# testSchematic.net
KiCad netlist of a schematic drawn in EAGLE
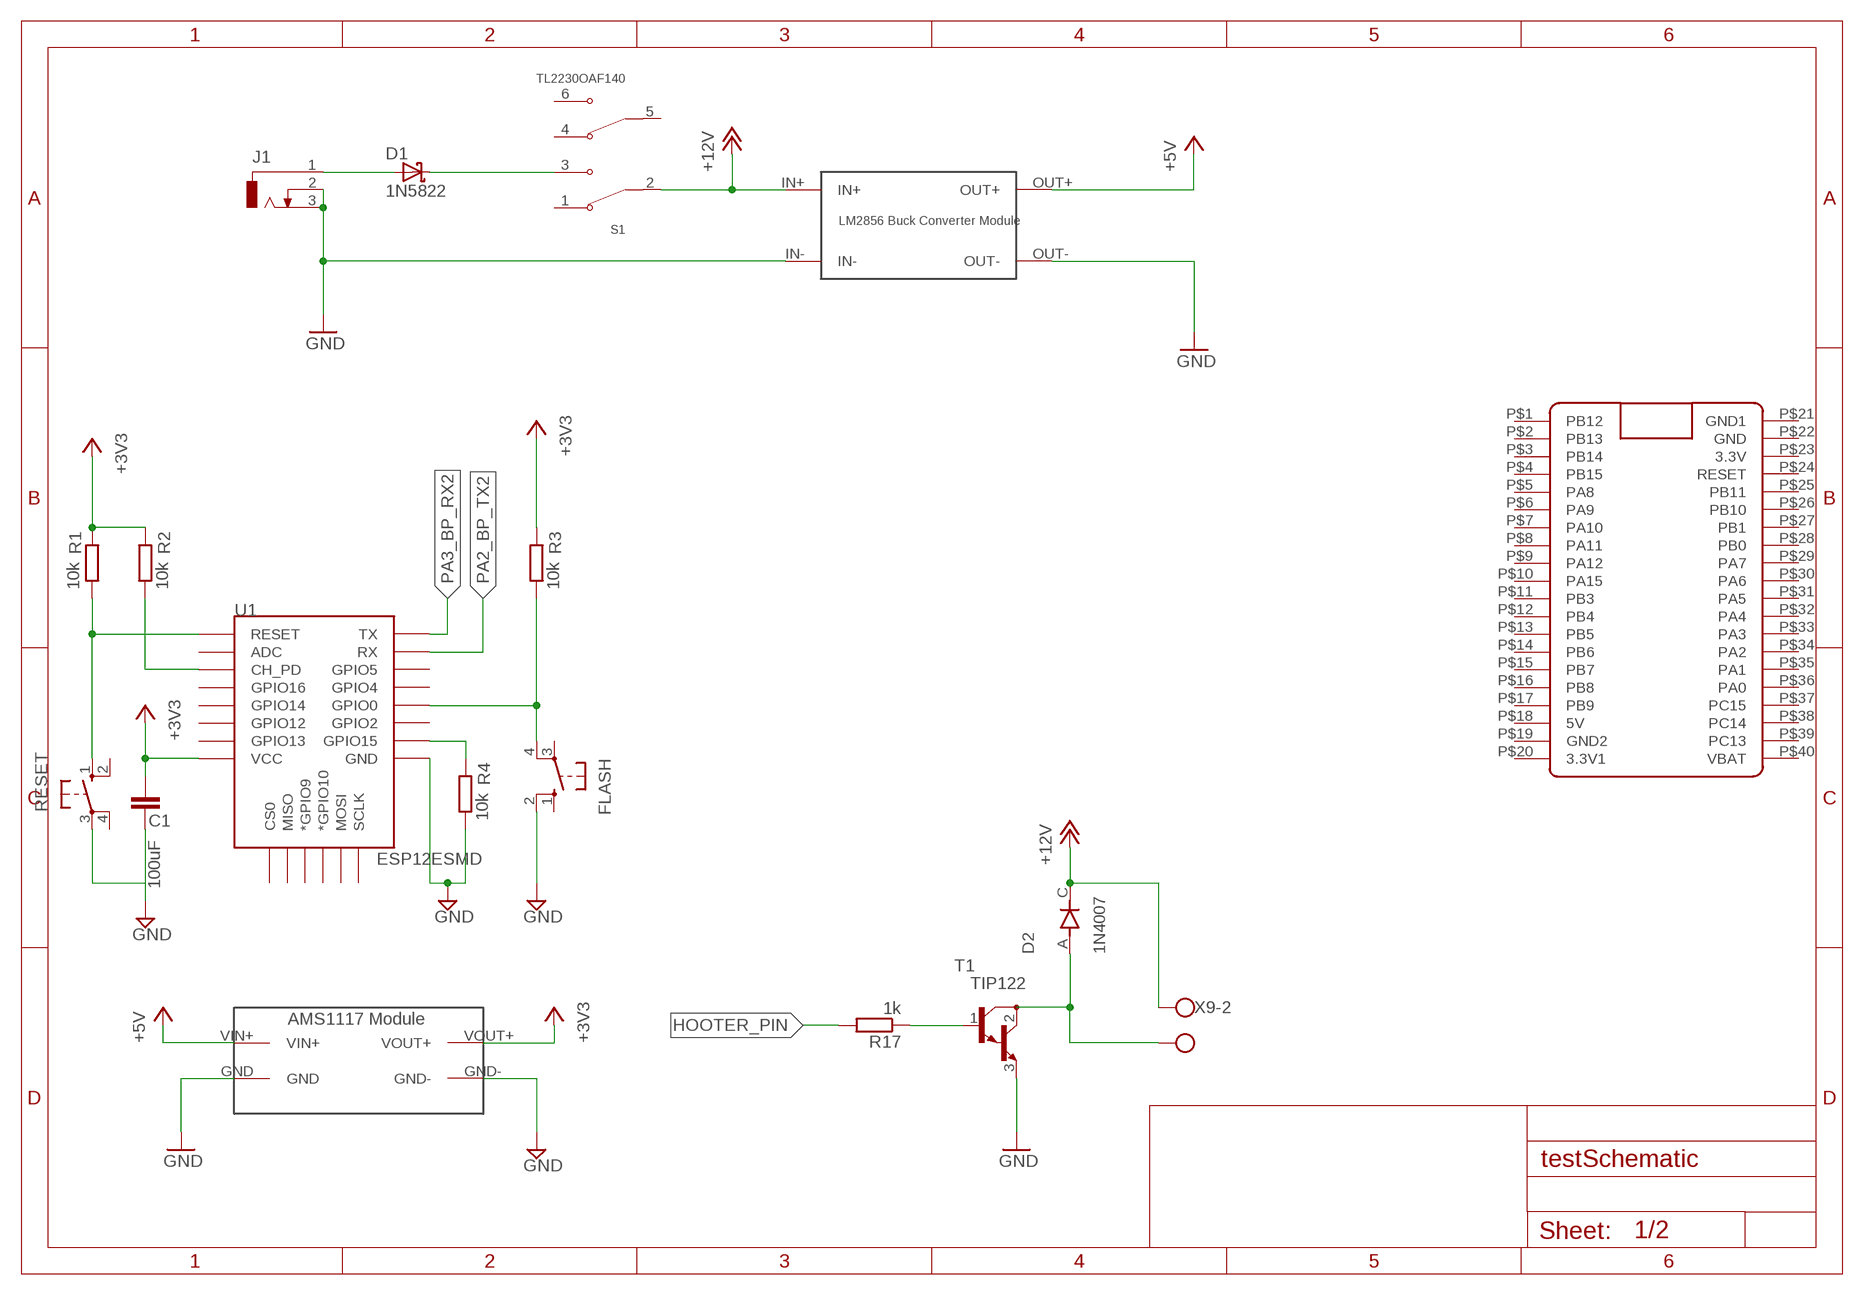
[diagram p0: schematic, sheet 1]
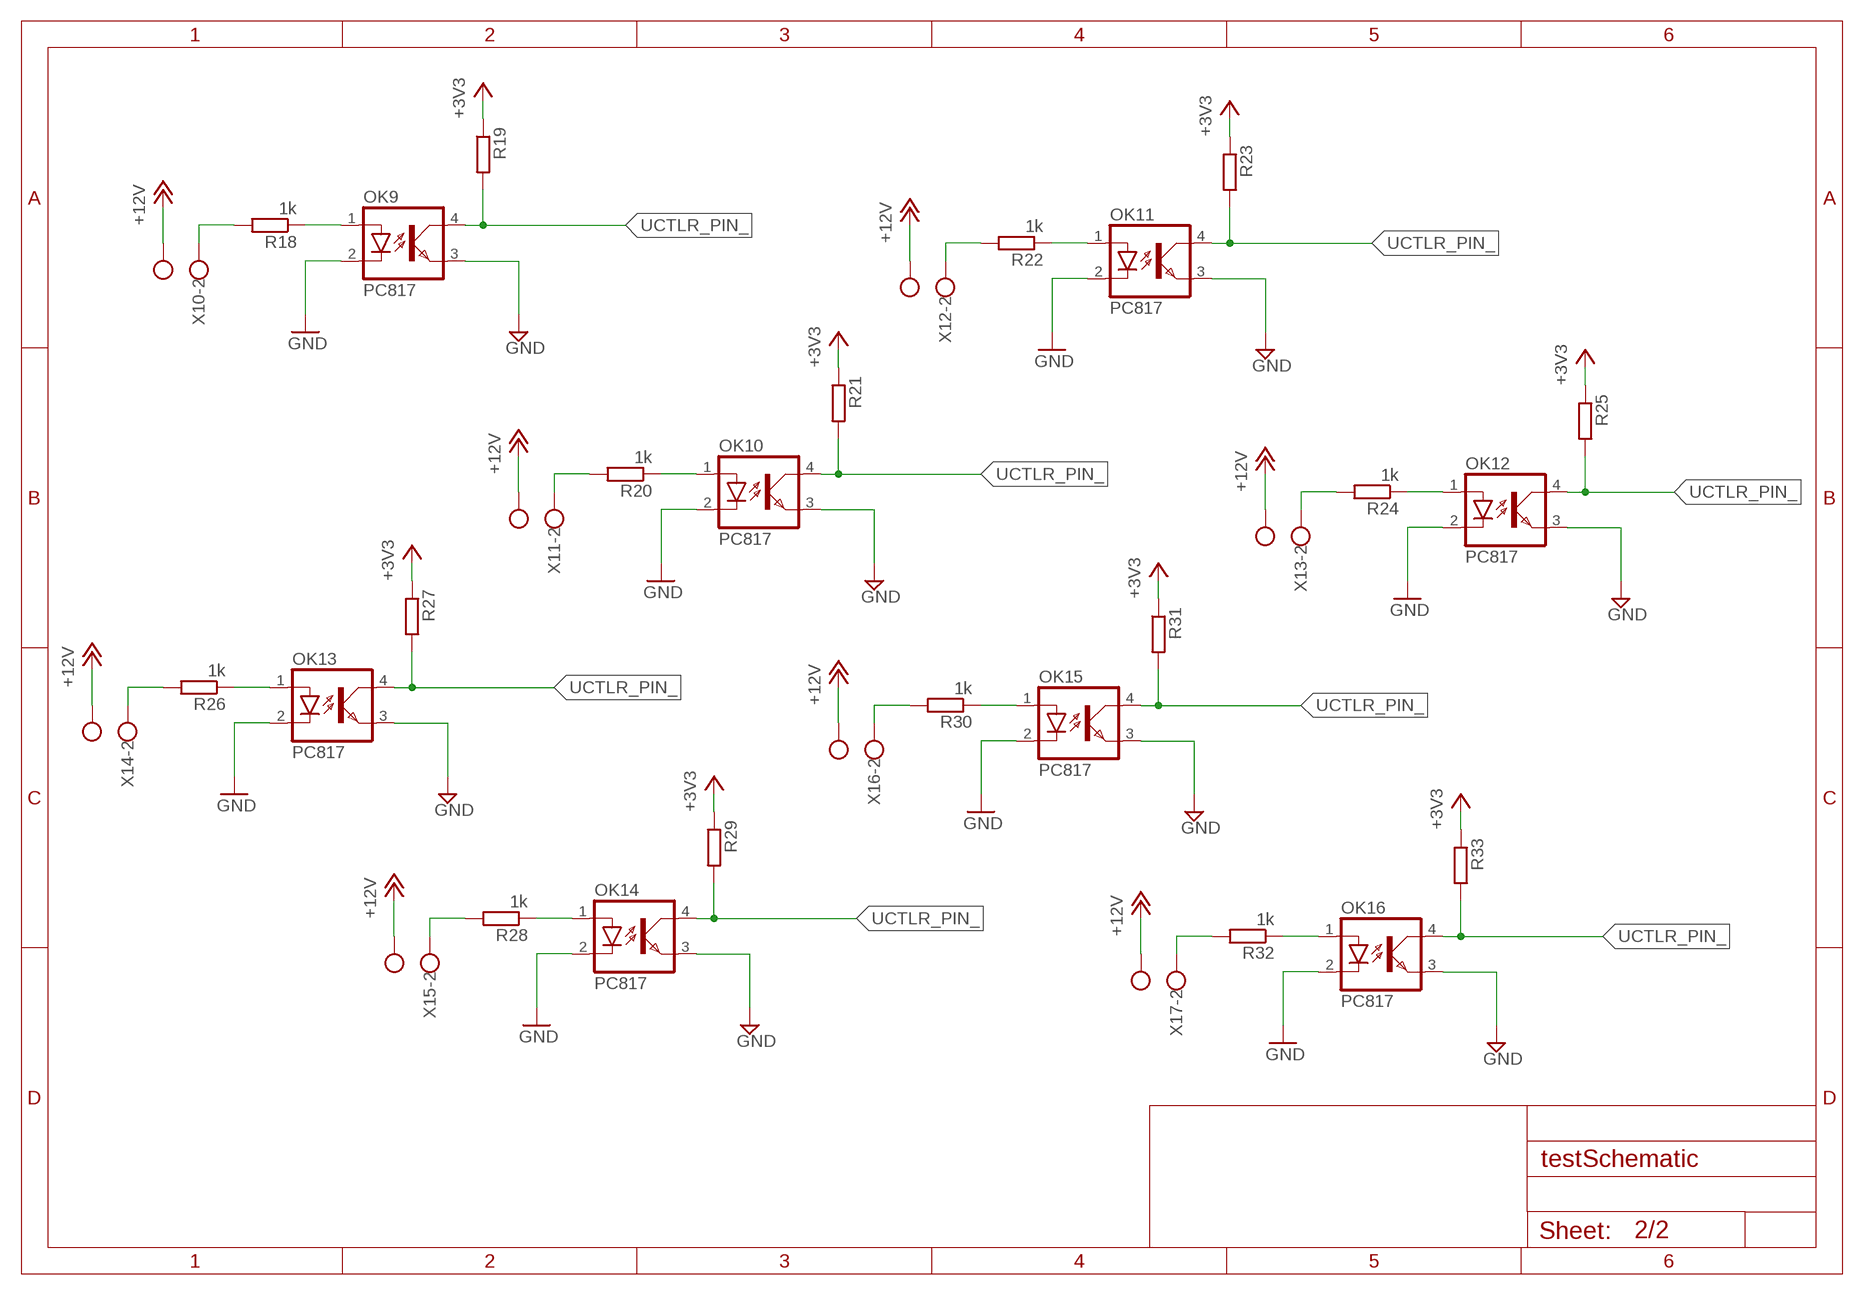
[diagram p1: schematic, sheet 2]

(export (version "E")
  (design (tool "Eeschema 10.0.6"))
  (components
    (comp (ref "C1")
      (value "100uF")
      (footprint "eagle-import:C2.5-3")
      (libsource (lib "eagle-import") (part "C2,5-3"))
    )
    (comp (ref "D1")
      (value "1N5822")
      (footprint "eagle-import:DIOAD2120W130L950D530P")
      (fields (field (name "MF") "ON Semiconductor"))
      (libsource (lib "eagle-import") (part "1N5822"))
    )
    (comp (ref "D2")
      (value "1N4007")
      (footprint "eagle-import:DIOAD1060W80L520D270")
      (fields (field (name "MF") "ON Semiconductor"))
      (libsource (lib "eagle-import") (part "1N4007"))
    )
    (comp (ref "FLASH")
      (value "10-XX")
      (footprint "eagle-import:B3F-10XX")
      (fields (field (name "MPN") "B3F-1000"))
      (libsource (lib "eagle-import") (part "10-XX"))
    )
    (comp (ref "J1")
      (value "DCJ0303")
      (footprint "eagle-import:DCJ0303")
      (libsource (lib "eagle-import") (part "DCJ0303"))
    )
    (comp (ref "R1")
      (value "10k")
      (footprint "eagle-import:0207_10")
      (libsource (lib "eagle-import") (part "R-EU_0207/10"))
    )
    (comp (ref "R2")
      (value "10k")
      (footprint "eagle-import:0207_10")
      (libsource (lib "eagle-import") (part "R-EU_0207/10"))
    )
    (comp (ref "R3")
      (value "10k")
      (footprint "eagle-import:0207_10")
      (libsource (lib "eagle-import") (part "R-EU_0207/10"))
    )
    (comp (ref "R4")
      (value "10k")
      (footprint "eagle-import:0207_10")
      (libsource (lib "eagle-import") (part "R-EU_0207/10"))
    )
    (comp (ref "R17")
      (value "1k")
      (footprint "eagle-import:0204_7")
      (libsource (lib "eagle-import") (part "R-EU_0204/7"))
    )
    (comp (ref "RESET")
      (value "10-XX")
      (footprint "eagle-import:B3F-10XX")
      (fields (field (name "MPN") "B3F-1000"))
      (libsource (lib "eagle-import") (part "10-XX"))
    )
    (comp (ref "S1")
      (value "TL2230OAF140")
      (footprint "eagle-import:SW_TL2230OAF140")
      (fields (field (name "MF") "E-Switch"))
      (libsource (lib "eagle-import") (part "TL2230OAF140"))
    )
    (comp (ref "T1")
      (value "TIP122")
      (footprint "eagle-import:TO220")
      (fields (field (name "MF") "onsemi"))
      (libsource (lib "eagle-import") (part "TIP122"))
    )
    (comp (ref "U$1")
      (value "BLUE_PILL")
      (footprint "eagle-import:BLUE_PILL")
      (libsource (lib "eagle-import") (part "BLUE_PILL"))
    )
    (comp (ref "U$2")
      (value "LM2596_MODULELM2569_MODULE")
      (footprint "eagle-import:LM2596_MODULE")
      (libsource (lib "eagle-import") (part "LM2596_MODULELM2569_MODULE"))
    )
    (comp (ref "U$3")
      (value "AMS1117_MODULE")
      (footprint "eagle-import:AMS1117_MODULE")
      (libsource (lib "eagle-import") (part "AMS1117_MODULE"))
    )
    (comp (ref "U1")
      (value "ESP12ESMD")
      (footprint "eagle-import:ESP12E-SMD")
      (fields (field (name "MF") "AI-Thinker") (field (name "MP") "ESP-12E"))
      (libsource (lib "eagle-import") (part "ESP12ESMD"))
    )
    (comp (ref "X9")
      (value "W237-102")
      (footprint "eagle-import:W237-102")
      (fields (field (name "MPN") "237-102"))
      (libsource (lib "eagle-import") (part "W237-102"))
    )
    (comp (ref "OK9")
      (value "PC817")
      (footprint "eagle-import:DIL04")
      (fields (field (name "MPN") "PC817X4J000F"))
      (libsource (lib "eagle-import") (part "PC817"))
    )
    (comp (ref "OK10")
      (value "PC817")
      (footprint "eagle-import:DIL04")
      (fields (field (name "MPN") "PC817X4J000F"))
      (libsource (lib "eagle-import") (part "PC817"))
    )
    (comp (ref "OK11")
      (value "PC817")
      (footprint "eagle-import:DIL04")
      (fields (field (name "MPN") "PC817X4J000F"))
      (libsource (lib "eagle-import") (part "PC817"))
    )
    (comp (ref "OK12")
      (value "PC817")
      (footprint "eagle-import:DIL04")
      (fields (field (name "MPN") "PC817X4J000F"))
      (libsource (lib "eagle-import") (part "PC817"))
    )
    (comp (ref "OK13")
      (value "PC817")
      (footprint "eagle-import:DIL04")
      (fields (field (name "MPN") "PC817X4J000F"))
      (libsource (lib "eagle-import") (part "PC817"))
    )
    (comp (ref "OK14")
      (value "PC817")
      (footprint "eagle-import:DIL04")
      (fields (field (name "MPN") "PC817X4J000F"))
      (libsource (lib "eagle-import") (part "PC817"))
    )
    (comp (ref "OK15")
      (value "PC817")
      (footprint "eagle-import:DIL04")
      (fields (field (name "MPN") "PC817X4J000F"))
      (libsource (lib "eagle-import") (part "PC817"))
    )
    (comp (ref "OK16")
      (value "PC817")
      (footprint "eagle-import:DIL04")
      (fields (field (name "MPN") "PC817X4J000F"))
      (libsource (lib "eagle-import") (part "PC817"))
    )
    (comp (ref "R18")
      (value "1k")
      (footprint "eagle-import:0204_7")
      (libsource (lib "eagle-import") (part "R-EU_0204/7"))
    )
    (comp (ref "R19")
      (value "R-EU_0204/7")
      (footprint "eagle-import:0204_7")
      (libsource (lib "eagle-import") (part "R-EU_0204/7"))
    )
    (comp (ref "R20")
      (value "1k")
      (footprint "eagle-import:0204_7")
      (libsource (lib "eagle-import") (part "R-EU_0204/7"))
    )
    (comp (ref "R21")
      (value "R-EU_0204/7")
      (footprint "eagle-import:0204_7")
      (libsource (lib "eagle-import") (part "R-EU_0204/7"))
    )
    (comp (ref "R22")
      (value "1k")
      (footprint "eagle-import:0204_7")
      (libsource (lib "eagle-import") (part "R-EU_0204/7"))
    )
    (comp (ref "R23")
      (value "R-EU_0204/7")
      (footprint "eagle-import:0204_7")
      (libsource (lib "eagle-import") (part "R-EU_0204/7"))
    )
    (comp (ref "R24")
      (value "1k")
      (footprint "eagle-import:0204_7")
      (libsource (lib "eagle-import") (part "R-EU_0204/7"))
    )
    (comp (ref "R25")
      (value "R-EU_0204/7")
      (footprint "eagle-import:0204_7")
      (libsource (lib "eagle-import") (part "R-EU_0204/7"))
    )
    (comp (ref "R26")
      (value "1k")
      (footprint "eagle-import:0204_7")
      (libsource (lib "eagle-import") (part "R-EU_0204/7"))
    )
    (comp (ref "R27")
      (value "R-EU_0204/7")
      (footprint "eagle-import:0204_7")
      (libsource (lib "eagle-import") (part "R-EU_0204/7"))
    )
    (comp (ref "R28")
      (value "1k")
      (footprint "eagle-import:0204_7")
      (libsource (lib "eagle-import") (part "R-EU_0204/7"))
    )
    (comp (ref "R29")
      (value "R-EU_0204/7")
      (footprint "eagle-import:0204_7")
      (libsource (lib "eagle-import") (part "R-EU_0204/7"))
    )
    (comp (ref "R30")
      (value "1k")
      (footprint "eagle-import:0204_7")
      (libsource (lib "eagle-import") (part "R-EU_0204/7"))
    )
    (comp (ref "R31")
      (value "R-EU_0204/7")
      (footprint "eagle-import:0204_7")
      (libsource (lib "eagle-import") (part "R-EU_0204/7"))
    )
    (comp (ref "R32")
      (value "1k")
      (footprint "eagle-import:0204_7")
      (libsource (lib "eagle-import") (part "R-EU_0204/7"))
    )
    (comp (ref "R33")
      (value "R-EU_0204/7")
      (footprint "eagle-import:0204_7")
      (libsource (lib "eagle-import") (part "R-EU_0204/7"))
    )
    (comp (ref "X10")
      (value "W237-102")
      (footprint "eagle-import:W237-102")
      (fields (field (name "MPN") "237-102"))
      (libsource (lib "eagle-import") (part "W237-102"))
    )
    (comp (ref "X11")
      (value "W237-102")
      (footprint "eagle-import:W237-102")
      (fields (field (name "MPN") "237-102"))
      (libsource (lib "eagle-import") (part "W237-102"))
    )
    (comp (ref "X12")
      (value "W237-102")
      (footprint "eagle-import:W237-102")
      (fields (field (name "MPN") "237-102"))
      (libsource (lib "eagle-import") (part "W237-102"))
    )
    (comp (ref "X13")
      (value "W237-102")
      (footprint "eagle-import:W237-102")
      (fields (field (name "MPN") "237-102"))
      (libsource (lib "eagle-import") (part "W237-102"))
    )
    (comp (ref "X14")
      (value "W237-102")
      (footprint "eagle-import:W237-102")
      (fields (field (name "MPN") "237-102"))
      (libsource (lib "eagle-import") (part "W237-102"))
    )
    (comp (ref "X15")
      (value "W237-102")
      (footprint "eagle-import:W237-102")
      (fields (field (name "MPN") "237-102"))
      (libsource (lib "eagle-import") (part "W237-102"))
    )
    (comp (ref "X16")
      (value "W237-102")
      (footprint "eagle-import:W237-102")
      (fields (field (name "MPN") "237-102"))
      (libsource (lib "eagle-import") (part "W237-102"))
    )
    (comp (ref "X17")
      (value "W237-102")
      (footprint "eagle-import:W237-102")
      (fields (field (name "MPN") "237-102"))
      (libsource (lib "eagle-import") (part "W237-102"))
    )
  )
  (nets
    (net (code "1") (name "+3V3") (class "Default")
      (node (ref "C1") (pin "2") (pinfunction "2_2") (pintype "passive"))
      (node (ref "R1") (pin "2") (pinfunction "2_2") (pintype "passive"))
      (node (ref "R19") (pin "1") (pinfunction "1_1") (pintype "passive"))
      (node (ref "R2") (pin "2") (pinfunction "2_2") (pintype "passive"))
      (node (ref "R21") (pin "1") (pinfunction "1_1") (pintype "passive"))
      (node (ref "R23") (pin "1") (pinfunction "1_1") (pintype "passive"))
      (node (ref "R25") (pin "1") (pinfunction "1_1") (pintype "passive"))
      (node (ref "R27") (pin "1") (pinfunction "1_1") (pintype "passive"))
      (node (ref "R29") (pin "1") (pinfunction "1_1") (pintype "passive"))
      (node (ref "R3") (pin "2") (pinfunction "2_2") (pintype "passive"))
      (node (ref "R31") (pin "1") (pinfunction "1_1") (pintype "passive"))
      (node (ref "R33") (pin "1") (pinfunction "1_1") (pintype "passive"))
      (node (ref "U$3") (pin "VOUT+") (pinfunction "VOUT+_VOUT+") (pintype "bidirectional"))
      (node (ref "U1") (pin "VCC") (pinfunction "VCC_VCC") (pintype "bidirectional"))
    )
    (net (code "2") (name "+5V") (class "Default")
      (node (ref "U$2") (pin "OUT+") (pinfunction "OUT+_OUT+") (pintype "bidirectional"))
      (node (ref "U$3") (pin "VIN+") (pinfunction "VIN+_VIN+") (pintype "bidirectional"))
    )
    (net (code "3") (name "+12V") (class "Default")
      (node (ref "D2") (pin "C") (pinfunction "C_C") (pintype "passive"))
      (node (ref "S1") (pin "2") (pinfunction "COM1_2") (pintype "passive"))
      (node (ref "U$2") (pin "IN+") (pinfunction "IN+_IN+") (pintype "bidirectional"))
      (node (ref "X10") (pin "1") (pinfunction "KL_1") (pintype "passive"))
      (node (ref "X11") (pin "1") (pinfunction "KL_1") (pintype "passive"))
      (node (ref "X12") (pin "1") (pinfunction "KL_1") (pintype "passive"))
      (node (ref "X13") (pin "1") (pinfunction "KL_1") (pintype "passive"))
      (node (ref "X14") (pin "1") (pinfunction "KL_1") (pintype "passive"))
      (node (ref "X15") (pin "1") (pinfunction "KL_1") (pintype "passive"))
      (node (ref "X16") (pin "1") (pinfunction "KL_1") (pintype "passive"))
      (node (ref "X17") (pin "1") (pinfunction "KL_1") (pintype "passive"))
      (node (ref "X9") (pin "2") (pinfunction "KL_2") (pintype "passive"))
    )
    (net (code "4") (name "GND") (class "Default")
      (node (ref "C1") (pin "1") (pinfunction "1_1") (pintype "passive"))
      (node (ref "FLASH") (pin "2") (pinfunction "S1_2") (pintype "passive"))
      (node (ref "J1") (pin "2") (pinfunction "2_2") (pintype "passive"))
      (node (ref "J1") (pin "3") (pinfunction "3_3") (pintype "passive"))
      (node (ref "OK10") (pin "2") (pinfunction "C_2") (pintype "passive"))
      (node (ref "OK10") (pin "3") (pinfunction "EMIT_3") (pintype "passive"))
      (node (ref "OK11") (pin "2") (pinfunction "C_2") (pintype "passive"))
      (node (ref "OK11") (pin "3") (pinfunction "EMIT_3") (pintype "passive"))
      (node (ref "OK12") (pin "2") (pinfunction "C_2") (pintype "passive"))
      (node (ref "OK12") (pin "3") (pinfunction "EMIT_3") (pintype "passive"))
      (node (ref "OK13") (pin "2") (pinfunction "C_2") (pintype "passive"))
      (node (ref "OK13") (pin "3") (pinfunction "EMIT_3") (pintype "passive"))
      (node (ref "OK14") (pin "2") (pinfunction "C_2") (pintype "passive"))
      (node (ref "OK14") (pin "3") (pinfunction "EMIT_3") (pintype "passive"))
      (node (ref "OK15") (pin "2") (pinfunction "C_2") (pintype "passive"))
      (node (ref "OK15") (pin "3") (pinfunction "EMIT_3") (pintype "passive"))
      (node (ref "OK16") (pin "2") (pinfunction "C_2") (pintype "passive"))
      (node (ref "OK16") (pin "3") (pinfunction "EMIT_3") (pintype "passive"))
      (node (ref "OK9") (pin "2") (pinfunction "C_2") (pintype "passive"))
      (node (ref "OK9") (pin "3") (pinfunction "EMIT_3") (pintype "passive"))
      (node (ref "R4") (pin "1") (pinfunction "1_1") (pintype "passive"))
      (node (ref "RESET") (pin "3") (pinfunction "P_3") (pintype "passive"))
      (node (ref "T1") (pin "3") (pinfunction "E_3") (pintype "passive"))
      (node (ref "U$2") (pin "IN-") (pinfunction "IN-_IN-") (pintype "bidirectional"))
      (node (ref "U$2") (pin "OUT-") (pinfunction "OUT-_OUT-") (pintype "bidirectional"))
      (node (ref "U$3") (pin "GND") (pinfunction "GND_GND") (pintype "bidirectional"))
      (node (ref "U$3") (pin "GND-") (pinfunction "GND-_GND-") (pintype "bidirectional"))
      (node (ref "U1") (pin "GND") (pinfunction "GND_GND") (pintype "bidirectional"))
    )
    (net (code "5") (name "GND1") (class "Default")
      (node (ref "U$1") (pin "P$21") (pinfunction "GND1_P$21") (pintype "power_in"))
    )
    (net (code "6") (name "HOOTER_PIN") (class "Default")
      (node (ref "R17") (pin "2") (pinfunction "2_2") (pintype "passive"))
    )
    (net (code "7") (name "Net-(D1-PadA)") (class "Default")
      (node (ref "D1") (pin "A") (pinfunction "A_A") (pintype "passive"))
      (node (ref "J1") (pin "1") (pinfunction "1_1") (pintype "passive"))
    )
    (net (code "8") (name "Net-(FLASH-P1)") (class "Default")
      (node (ref "FLASH") (pin "4") (pinfunction "P1_4") (pintype "passive"))
      (node (ref "R3") (pin "1") (pinfunction "1_1") (pintype "passive"))
      (node (ref "U1") (pin "GPIO0") (pinfunction "GPIO0_GPIO0") (pintype "bidirectional"))
    )
    (net (code "9") (name "Net-(OK9-A)") (class "Default")
      (node (ref "OK9") (pin "1") (pinfunction "A_1") (pintype "passive"))
      (node (ref "R18") (pin "1") (pinfunction "1_1") (pintype "passive"))
    )
    (net (code "10") (name "Net-(OK10-A)") (class "Default")
      (node (ref "OK10") (pin "1") (pinfunction "A_1") (pintype "passive"))
      (node (ref "R20") (pin "1") (pinfunction "1_1") (pintype "passive"))
    )
    (net (code "11") (name "Net-(OK11-A)") (class "Default")
      (node (ref "OK11") (pin "1") (pinfunction "A_1") (pintype "passive"))
      (node (ref "R22") (pin "1") (pinfunction "1_1") (pintype "passive"))
    )
    (net (code "12") (name "Net-(OK12-A)") (class "Default")
      (node (ref "OK12") (pin "1") (pinfunction "A_1") (pintype "passive"))
      (node (ref "R24") (pin "1") (pinfunction "1_1") (pintype "passive"))
    )
    (net (code "13") (name "Net-(OK13-A)") (class "Default")
      (node (ref "OK13") (pin "1") (pinfunction "A_1") (pintype "passive"))
      (node (ref "R26") (pin "1") (pinfunction "1_1") (pintype "passive"))
    )
    (net (code "14") (name "Net-(OK14-A)") (class "Default")
      (node (ref "OK14") (pin "1") (pinfunction "A_1") (pintype "passive"))
      (node (ref "R28") (pin "1") (pinfunction "1_1") (pintype "passive"))
    )
    (net (code "15") (name "Net-(OK15-A)") (class "Default")
      (node (ref "OK15") (pin "1") (pinfunction "A_1") (pintype "passive"))
      (node (ref "R30") (pin "1") (pinfunction "1_1") (pintype "passive"))
    )
    (net (code "16") (name "Net-(OK16-A)") (class "Default")
      (node (ref "OK16") (pin "1") (pinfunction "A_1") (pintype "passive"))
      (node (ref "R32") (pin "1") (pinfunction "1_1") (pintype "passive"))
    )
    (net (code "17") (name "Net-(R2-Pad1)") (class "Default")
      (node (ref "R2") (pin "1") (pinfunction "1_1") (pintype "passive"))
      (node (ref "U1") (pin "CH_PD") (pinfunction "CH_PD_CH_PD") (pintype "bidirectional"))
    )
    (net (code "18") (name "Net-(R4-Pad2)") (class "Default")
      (node (ref "R4") (pin "2") (pinfunction "2_2") (pintype "passive"))
      (node (ref "U1") (pin "GPIO15") (pinfunction "GPIO15_GPIO15") (pintype "bidirectional"))
    )
    (net (code "19") (name "Net-(RESET-S)") (class "Default")
      (node (ref "R1") (pin "1") (pinfunction "1_1") (pintype "passive"))
      (node (ref "RESET") (pin "1") (pinfunction "S_1") (pintype "passive"))
      (node (ref "U1") (pin "RESET") (pinfunction "RESET_RESET") (pintype "bidirectional"))
    )
    (net (code "20") (name "Net-(S1-NO1)") (class "Default")
      (node (ref "D1") (pin "C") (pinfunction "C_C") (pintype "passive"))
      (node (ref "S1") (pin "3") (pinfunction "NO1_3") (pintype "passive"))
    )
    (net (code "21") (name "Net-(T1-B)") (class "Default")
      (node (ref "R17") (pin "1") (pinfunction "1_1") (pintype "passive"))
      (node (ref "T1") (pin "1") (pinfunction "B_1") (pintype "passive"))
    )
    (net (code "22") (name "Net-(T1-C)") (class "Default")
      (node (ref "D2") (pin "A") (pinfunction "A_A") (pintype "passive"))
      (node (ref "T1") (pin "2") (pinfunction "C_2") (pintype "passive"))
      (node (ref "X9") (pin "1") (pinfunction "KL_1") (pintype "passive"))
    )
    (net (code "23") (name "Net-(X10B-KL)") (class "Default")
      (node (ref "R18") (pin "2") (pinfunction "2_2") (pintype "passive"))
      (node (ref "X10") (pin "2") (pinfunction "KL_2") (pintype "passive"))
    )
    (net (code "24") (name "Net-(X11B-KL)") (class "Default")
      (node (ref "R20") (pin "2") (pinfunction "2_2") (pintype "passive"))
      (node (ref "X11") (pin "2") (pinfunction "KL_2") (pintype "passive"))
    )
    (net (code "25") (name "Net-(X12B-KL)") (class "Default")
      (node (ref "R22") (pin "2") (pinfunction "2_2") (pintype "passive"))
      (node (ref "X12") (pin "2") (pinfunction "KL_2") (pintype "passive"))
    )
    (net (code "26") (name "Net-(X13B-KL)") (class "Default")
      (node (ref "R24") (pin "2") (pinfunction "2_2") (pintype "passive"))
      (node (ref "X13") (pin "2") (pinfunction "KL_2") (pintype "passive"))
    )
    (net (code "27") (name "Net-(X14B-KL)") (class "Default")
      (node (ref "R26") (pin "2") (pinfunction "2_2") (pintype "passive"))
      (node (ref "X14") (pin "2") (pinfunction "KL_2") (pintype "passive"))
    )
    (net (code "28") (name "Net-(X15B-KL)") (class "Default")
      (node (ref "R28") (pin "2") (pinfunction "2_2") (pintype "passive"))
      (node (ref "X15") (pin "2") (pinfunction "KL_2") (pintype "passive"))
    )
    (net (code "29") (name "Net-(X16B-KL)") (class "Default")
      (node (ref "R30") (pin "2") (pinfunction "2_2") (pintype "passive"))
      (node (ref "X16") (pin "2") (pinfunction "KL_2") (pintype "passive"))
    )
    (net (code "30") (name "Net-(X17B-KL)") (class "Default")
      (node (ref "R32") (pin "2") (pinfunction "2_2") (pintype "passive"))
      (node (ref "X17") (pin "2") (pinfunction "KL_2") (pintype "passive"))
    )
    (net (code "31") (name "PA2_BP_TX2") (class "Default")
      (node (ref "U1") (pin "RXD0") (pinfunction "RX_RXD0") (pintype "bidirectional"))
    )
    (net (code "32") (name "PA3_BP_RX2") (class "Default")
      (node (ref "U1") (pin "TXD0") (pinfunction "TX_TXD0") (pintype "bidirectional"))
    )
    (net (code "33") (name "UCTLR_PIN_") (class "Default")
      (node (ref "OK10") (pin "4") (pinfunction "COL_4") (pintype "passive"))
      (node (ref "OK11") (pin "4") (pinfunction "COL_4") (pintype "passive"))
      (node (ref "OK12") (pin "4") (pinfunction "COL_4") (pintype "passive"))
      (node (ref "OK13") (pin "4") (pinfunction "COL_4") (pintype "passive"))
      (node (ref "OK14") (pin "4") (pinfunction "COL_4") (pintype "passive"))
      (node (ref "OK15") (pin "4") (pinfunction "COL_4") (pintype "passive"))
      (node (ref "OK16") (pin "4") (pinfunction "COL_4") (pintype "passive"))
      (node (ref "OK9") (pin "4") (pinfunction "COL_4") (pintype "passive"))
      (node (ref "R19") (pin "2") (pinfunction "2_2") (pintype "passive"))
      (node (ref "R21") (pin "2") (pinfunction "2_2") (pintype "passive"))
      (node (ref "R23") (pin "2") (pinfunction "2_2") (pintype "passive"))
      (node (ref "R25") (pin "2") (pinfunction "2_2") (pintype "passive"))
      (node (ref "R27") (pin "2") (pinfunction "2_2") (pintype "passive"))
      (node (ref "R29") (pin "2") (pinfunction "2_2") (pintype "passive"))
      (node (ref "R31") (pin "2") (pinfunction "2_2") (pintype "passive"))
      (node (ref "R33") (pin "2") (pinfunction "2_2") (pintype "passive"))
    )
    (net (code "34") (name "unconnected-(FLASH-P-Pad3)") (class "Default")
      (node (ref "FLASH") (pin "3") (pinfunction "P_3") (pintype "passive"))
    )
    (net (code "35") (name "unconnected-(FLASH-S-Pad1)") (class "Default")
      (node (ref "FLASH") (pin "1") (pinfunction "S_1") (pintype "passive"))
    )
    (net (code "36") (name "unconnected-(RESET-P1-Pad4)") (class "Default")
      (node (ref "RESET") (pin "4") (pinfunction "P1_4") (pintype "passive"))
    )
    (net (code "37") (name "unconnected-(RESET-S1-Pad2)") (class "Default")
      (node (ref "RESET") (pin "2") (pinfunction "S1_2") (pintype "passive"))
    )
    (net (code "38") (name "unconnected-(S1-COM2-Pad5)") (class "Default")
      (node (ref "S1") (pin "5") (pinfunction "COM2_5") (pintype "passive"))
    )
    (net (code "39") (name "unconnected-(S1-NC1-Pad1)") (class "Default")
      (node (ref "S1") (pin "1") (pinfunction "NC1_1") (pintype "passive"))
    )
    (net (code "40") (name "unconnected-(S1-NC2-Pad4)") (class "Default")
      (node (ref "S1") (pin "4") (pinfunction "NC2_4") (pintype "passive"))
    )
    (net (code "41") (name "unconnected-(S1-NO2-Pad6)") (class "Default")
      (node (ref "S1") (pin "6") (pinfunction "NO2_6") (pintype "passive"))
    )
    (net (code "42") (name "unconnected-(U$1-3.3V-PadP$23)") (class "Default")
      (node (ref "U$1") (pin "P$23") (pinfunction "3.3V_P$23") (pintype "bidirectional"))
    )
    (net (code "43") (name "unconnected-(U$1-3.3V1-PadP$20)") (class "Default")
      (node (ref "U$1") (pin "P$20") (pinfunction "3.3V1_P$20") (pintype "bidirectional"))
    )
    (net (code "44") (name "unconnected-(U$1-5V-PadP$18)") (class "Default")
      (node (ref "U$1") (pin "P$18") (pinfunction "5V_P$18") (pintype "bidirectional"))
    )
    (net (code "45") (name "unconnected-(U$1-GND-PadP$22)") (class "Default")
      (node (ref "U$1") (pin "P$22") (pinfunction "GND_P$22") (pintype "bidirectional"))
    )
    (net (code "46") (name "unconnected-(U$1-GND2-PadP$19)") (class "Default")
      (node (ref "U$1") (pin "P$19") (pinfunction "GND2_P$19") (pintype "bidirectional"))
    )
    (net (code "47") (name "unconnected-(U$1-PA0-PadP$36)") (class "Default")
      (node (ref "U$1") (pin "P$36") (pinfunction "PA0_P$36") (pintype "bidirectional"))
    )
    (net (code "48") (name "unconnected-(U$1-PA1-PadP$35)") (class "Default")
      (node (ref "U$1") (pin "P$35") (pinfunction "PA1_P$35") (pintype "bidirectional"))
    )
    (net (code "49") (name "unconnected-(U$1-PA2-PadP$34)") (class "Default")
      (node (ref "U$1") (pin "P$34") (pinfunction "PA2_P$34") (pintype "bidirectional"))
    )
    (net (code "50") (name "unconnected-(U$1-PA3-PadP$33)") (class "Default")
      (node (ref "U$1") (pin "P$33") (pinfunction "PA3_P$33") (pintype "bidirectional"))
    )
    (net (code "51") (name "unconnected-(U$1-PA4-PadP$32)") (class "Default")
      (node (ref "U$1") (pin "P$32") (pinfunction "PA4_P$32") (pintype "bidirectional"))
    )
    (net (code "52") (name "unconnected-(U$1-PA5-PadP$31)") (class "Default")
      (node (ref "U$1") (pin "P$31") (pinfunction "PA5_P$31") (pintype "bidirectional"))
    )
    (net (code "53") (name "unconnected-(U$1-PA6-PadP$30)") (class "Default")
      (node (ref "U$1") (pin "P$30") (pinfunction "PA6_P$30") (pintype "bidirectional"))
    )
    (net (code "54") (name "unconnected-(U$1-PA7-PadP$29)") (class "Default")
      (node (ref "U$1") (pin "P$29") (pinfunction "PA7_P$29") (pintype "bidirectional"))
    )
    (net (code "55") (name "unconnected-(U$1-PA8-PadP$5)") (class "Default")
      (node (ref "U$1") (pin "P$5") (pinfunction "PA8_P$5") (pintype "bidirectional"))
    )
    (net (code "56") (name "unconnected-(U$1-PA9-PadP$6)") (class "Default")
      (node (ref "U$1") (pin "P$6") (pinfunction "PA9_P$6") (pintype "bidirectional"))
    )
    (net (code "57") (name "unconnected-(U$1-PA10-PadP$7)") (class "Default")
      (node (ref "U$1") (pin "P$7") (pinfunction "PA10_P$7") (pintype "bidirectional"))
    )
    (net (code "58") (name "unconnected-(U$1-PA11-PadP$8)") (class "Default")
      (node (ref "U$1") (pin "P$8") (pinfunction "PA11_P$8") (pintype "bidirectional"))
    )
    (net (code "59") (name "unconnected-(U$1-PA12-PadP$9)") (class "Default")
      (node (ref "U$1") (pin "P$9") (pinfunction "PA12_P$9") (pintype "bidirectional"))
    )
    (net (code "60") (name "unconnected-(U$1-PA15-PadP$10)") (class "Default")
      (node (ref "U$1") (pin "P$10") (pinfunction "PA15_P$10") (pintype "bidirectional"))
    )
    (net (code "61") (name "unconnected-(U$1-PB0-PadP$28)") (class "Default")
      (node (ref "U$1") (pin "P$28") (pinfunction "PB0_P$28") (pintype "bidirectional"))
    )
    (net (code "62") (name "unconnected-(U$1-PB1-PadP$27)") (class "Default")
      (node (ref "U$1") (pin "P$27") (pinfunction "PB1_P$27") (pintype "bidirectional"))
    )
    (net (code "63") (name "unconnected-(U$1-PB3-PadP$11)") (class "Default")
      (node (ref "U$1") (pin "P$11") (pinfunction "PB3_P$11") (pintype "bidirectional"))
    )
    (net (code "64") (name "unconnected-(U$1-PB4-PadP$12)") (class "Default")
      (node (ref "U$1") (pin "P$12") (pinfunction "PB4_P$12") (pintype "bidirectional"))
    )
    (net (code "65") (name "unconnected-(U$1-PB5-PadP$13)") (class "Default")
      (node (ref "U$1") (pin "P$13") (pinfunction "PB5_P$13") (pintype "bidirectional"))
    )
    (net (code "66") (name "unconnected-(U$1-PB6-PadP$14)") (class "Default")
      (node (ref "U$1") (pin "P$14") (pinfunction "PB6_P$14") (pintype "bidirectional"))
    )
    (net (code "67") (name "unconnected-(U$1-PB7-PadP$15)") (class "Default")
      (node (ref "U$1") (pin "P$15") (pinfunction "PB7_P$15") (pintype "bidirectional"))
    )
    (net (code "68") (name "unconnected-(U$1-PB8-PadP$16)") (class "Default")
      (node (ref "U$1") (pin "P$16") (pinfunction "PB8_P$16") (pintype "bidirectional"))
    )
    (net (code "69") (name "unconnected-(U$1-PB9-PadP$17)") (class "Default")
      (node (ref "U$1") (pin "P$17") (pinfunction "PB9_P$17") (pintype "bidirectional"))
    )
    (net (code "70") (name "unconnected-(U$1-PB10-PadP$26)") (class "Default")
      (node (ref "U$1") (pin "P$26") (pinfunction "PB10_P$26") (pintype "bidirectional"))
    )
    (net (code "71") (name "unconnected-(U$1-PB11-PadP$25)") (class "Default")
      (node (ref "U$1") (pin "P$25") (pinfunction "PB11_P$25") (pintype "bidirectional"))
    )
    (net (code "72") (name "unconnected-(U$1-PB12-PadP$1)") (class "Default")
      (node (ref "U$1") (pin "P$1") (pinfunction "PB12_P$1") (pintype "bidirectional"))
    )
    (net (code "73") (name "unconnected-(U$1-PB13-PadP$2)") (class "Default")
      (node (ref "U$1") (pin "P$2") (pinfunction "PB13_P$2") (pintype "bidirectional"))
    )
    (net (code "74") (name "unconnected-(U$1-PB14-PadP$3)") (class "Default")
      (node (ref "U$1") (pin "P$3") (pinfunction "PB14_P$3") (pintype "bidirectional"))
    )
    (net (code "75") (name "unconnected-(U$1-PB15-PadP$4)") (class "Default")
      (node (ref "U$1") (pin "P$4") (pinfunction "PB15_P$4") (pintype "bidirectional"))
    )
    (net (code "76") (name "unconnected-(U$1-PC13-PadP$39)") (class "Default")
      (node (ref "U$1") (pin "P$39") (pinfunction "PC13_P$39") (pintype "bidirectional"))
    )
    (net (code "77") (name "unconnected-(U$1-PC14-PadP$38)") (class "Default")
      (node (ref "U$1") (pin "P$38") (pinfunction "PC14_P$38") (pintype "bidirectional"))
    )
    (net (code "78") (name "unconnected-(U$1-PC15-PadP$37)") (class "Default")
      (node (ref "U$1") (pin "P$37") (pinfunction "PC15_P$37") (pintype "bidirectional"))
    )
    (net (code "79") (name "unconnected-(U$1-RESET-PadP$24)") (class "Default")
      (node (ref "U$1") (pin "P$24") (pinfunction "RESET_P$24") (pintype "bidirectional"))
    )
    (net (code "80") (name "unconnected-(U$1-VBAT-PadP$40)") (class "Default")
      (node (ref "U$1") (pin "P$40") (pinfunction "VBAT_P$40") (pintype "bidirectional"))
    )
    (net (code "81") (name "unconnected-(U1-*GPIO9-PadGPIO9)") (class "Default")
      (node (ref "U1") (pin "GPIO9") (pinfunction "*GPIO9_GPIO9") (pintype "bidirectional"))
    )
    (net (code "82") (name "unconnected-(U1-*GPIO10-PadGPIO10)") (class "Default")
      (node (ref "U1") (pin "GPIO10") (pinfunction "*GPIO10_GPIO10") (pintype "bidirectional"))
    )
    (net (code "83") (name "unconnected-(U1-PadADC)") (class "Default")
      (node (ref "U1") (pin "ADC") (pinfunction "ADC_ADC") (pintype "bidirectional"))
    )
    (net (code "84") (name "unconnected-(U1-PadCS0)") (class "Default")
      (node (ref "U1") (pin "CS0") (pinfunction "CS0_CS0") (pintype "bidirectional"))
    )
    (net (code "85") (name "unconnected-(U1-PadGPIO2)") (class "Default")
      (node (ref "U1") (pin "GPIO2") (pinfunction "GPIO2_GPIO2") (pintype "bidirectional"))
    )
    (net (code "86") (name "unconnected-(U1-PadGPIO4)") (class "Default")
      (node (ref "U1") (pin "GPIO4") (pinfunction "GPIO4_GPIO4") (pintype "bidirectional"))
    )
    (net (code "87") (name "unconnected-(U1-PadGPIO5)") (class "Default")
      (node (ref "U1") (pin "GPIO5") (pinfunction "GPIO5_GPIO5") (pintype "bidirectional"))
    )
    (net (code "88") (name "unconnected-(U1-PadGPIO12)") (class "Default")
      (node (ref "U1") (pin "GPIO12") (pinfunction "GPIO12_GPIO12") (pintype "bidirectional"))
    )
    (net (code "89") (name "unconnected-(U1-PadGPIO13)") (class "Default")
      (node (ref "U1") (pin "GPIO13") (pinfunction "GPIO13_GPIO13") (pintype "bidirectional"))
    )
    (net (code "90") (name "unconnected-(U1-PadGPIO14)") (class "Default")
      (node (ref "U1") (pin "GPIO14") (pinfunction "GPIO14_GPIO14") (pintype "bidirectional"))
    )
    (net (code "91") (name "unconnected-(U1-PadGPIO16)") (class "Default")
      (node (ref "U1") (pin "GPIO16") (pinfunction "GPIO16_GPIO16") (pintype "bidirectional"))
    )
    (net (code "92") (name "unconnected-(U1-PadMISO)") (class "Default")
      (node (ref "U1") (pin "MISO") (pinfunction "MISO_MISO") (pintype "bidirectional"))
    )
    (net (code "93") (name "unconnected-(U1-PadMOSI)") (class "Default")
      (node (ref "U1") (pin "MOSI") (pinfunction "MOSI_MOSI") (pintype "bidirectional"))
    )
    (net (code "94") (name "unconnected-(U1-PadSCLK)") (class "Default")
      (node (ref "U1") (pin "SCLK") (pinfunction "SCLK_SCLK") (pintype "bidirectional"))
    )
  )
)
